# Sensors.net
KiCad netlist of a schematic drawn in Altium Designer
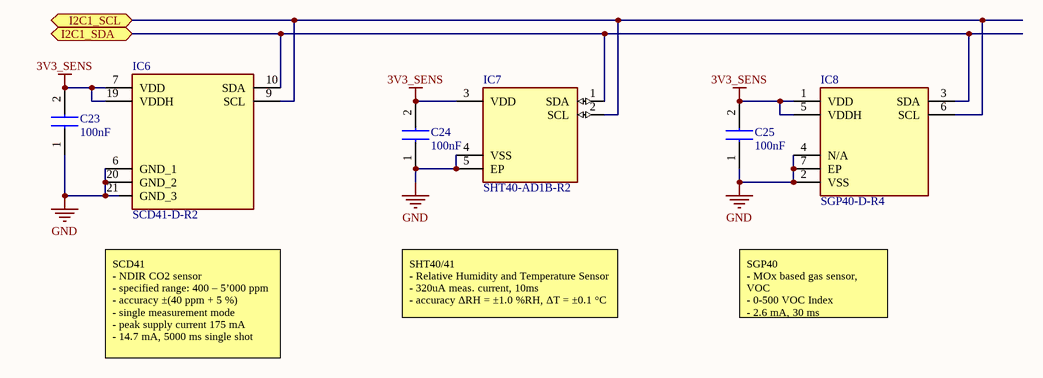
[diagram p0: Sensors.SchDoc]

(export (version "E")
  (design (tool "Eeschema 10.0.6"))
  (components
    (comp (ref "C23")
      (value "100nF")
      (footprint "SamacSys:CAPC1005X70N")
      (description "Capacitor")
      (fields
        (field (name "MANUFACTURER_PART_NUMBER") "GRM155R61A104KA01D")
        (field (name "MOUSER PART NUMBER") "81-GRM155R61A104KA01")
      )
      (libsource (lib "*") (part "GRM155R61A104KA01D"))
    )
    (comp (ref "C24")
      (value "100nF")
      (footprint "SamacSys:CAPC1005X70N")
      (description "Capacitor")
      (fields
        (field (name "MANUFACTURER_PART_NUMBER") "GRM155R61A104KA01D")
        (field (name "MOUSER PART NUMBER") "81-GRM155R61A104KA01")
      )
      (libsource (lib "*") (part "GRM155R61A104KA01D"))
    )
    (comp (ref "C25")
      (value "100nF")
      (footprint "SamacSys:CAPC1005X70N")
      (description "Capacitor")
      (fields
        (field (name "MANUFACTURER_PART_NUMBER") "GRM155R61A104KA01D")
        (field (name "MOUSER PART NUMBER") "81-GRM155R61A104KA01")
      )
      (libsource (lib "*") (part "GRM155R61A104KA01D"))
    )
    (comp (ref "IC6")
      (value "SCD41-D-R2")
      (footprint "SamacSys:SCD41DR2")
      (description "Integrated Circuit")
      (fields (field (name "MOUSER PART NUMBER") "403-SCD41-D-R2"))
      (libsource (lib "SamacSys") (part "SCD41-D-R2"))
    )
    (comp (ref "IC7")
      (value "SHT40-AD1B-R2")
      (footprint "SamacSys:SON80P150X150X59-5N")
      (description "Integrated Circuit")
      (fields (field (name "MOUSER PART NUMBER") "403-SHT40-AD1B-R2"))
      (libsource (lib "SamacSys") (part "SHT40-AD1B-R2"))
    )
    (comp (ref "IC8")
      (value "SGP40-D-R4")
      (footprint "SamacSys:SON80P244X244X95-7N")
      (description "Integrated Circuit")
      (fields (field (name "MOUSER PART NUMBER") "403-SGP40-D-R4"))
      (libsource (lib "SamacSys") (part "SGP40-D-R4"))
    )
  )
  (nets
    (net (code "1") (name "/I2C1_SCL") (class "Default")
      (node (ref "IC6") (pin "9") (pinfunction "SCL_9") (pintype "passive"))
      (node (ref "IC7") (pin "2") (pinfunction "SCL_2") (pintype "bidirectional"))
      (node (ref "IC8") (pin "6") (pinfunction "SCL_6") (pintype "passive"))
    )
    (net (code "2") (name "/I2C1_SDA") (class "Default")
      (node (ref "IC6") (pin "10") (pinfunction "SDA_10") (pintype "passive"))
      (node (ref "IC7") (pin "1") (pinfunction "SDA_1") (pintype "bidirectional"))
      (node (ref "IC8") (pin "3") (pinfunction "SDA_3") (pintype "passive"))
    )
    (net (code "3") (name "3V3_SENS") (class "Default")
      (node (ref "C23") (pin "2") (pinfunction "2_2") (pintype "passive"))
      (node (ref "C24") (pin "2") (pinfunction "2_2") (pintype "passive"))
      (node (ref "C25") (pin "2") (pinfunction "2_2") (pintype "passive"))
      (node (ref "IC6") (pin "19") (pinfunction "VDDH_19") (pintype "passive"))
      (node (ref "IC6") (pin "7") (pinfunction "VDD_7") (pintype "passive"))
      (node (ref "IC7") (pin "3") (pinfunction "VDD_3") (pintype "power_in"))
      (node (ref "IC8") (pin "1") (pinfunction "VDD_1") (pintype "passive"))
      (node (ref "IC8") (pin "5") (pinfunction "VDDH_5") (pintype "passive"))
    )
    (net (code "4") (name "GND") (class "Default")
      (node (ref "C23") (pin "1") (pinfunction "1_1") (pintype "passive"))
      (node (ref "C24") (pin "1") (pinfunction "1_1") (pintype "passive"))
      (node (ref "C25") (pin "1") (pinfunction "1_1") (pintype "passive"))
      (node (ref "IC6") (pin "20") (pinfunction "GND_2_20") (pintype "passive"))
      (node (ref "IC6") (pin "21") (pinfunction "GND_3_21") (pintype "passive"))
      (node (ref "IC6") (pin "6") (pinfunction "GND_1_6") (pintype "passive"))
      (node (ref "IC7") (pin "4") (pinfunction "VSS_4") (pintype "power_in"))
      (node (ref "IC7") (pin "5") (pinfunction "EP_5") (pintype "power_in"))
      (node (ref "IC8") (pin "2") (pinfunction "VSS_2") (pintype "passive"))
      (node (ref "IC8") (pin "4") (pinfunction "N/A_4") (pintype "passive"))
      (node (ref "IC8") (pin "7") (pinfunction "EP_7") (pintype "passive"))
    )
  )
)
